# USBHUB.net
KiCad netlist of a schematic drawn in Altium Designer
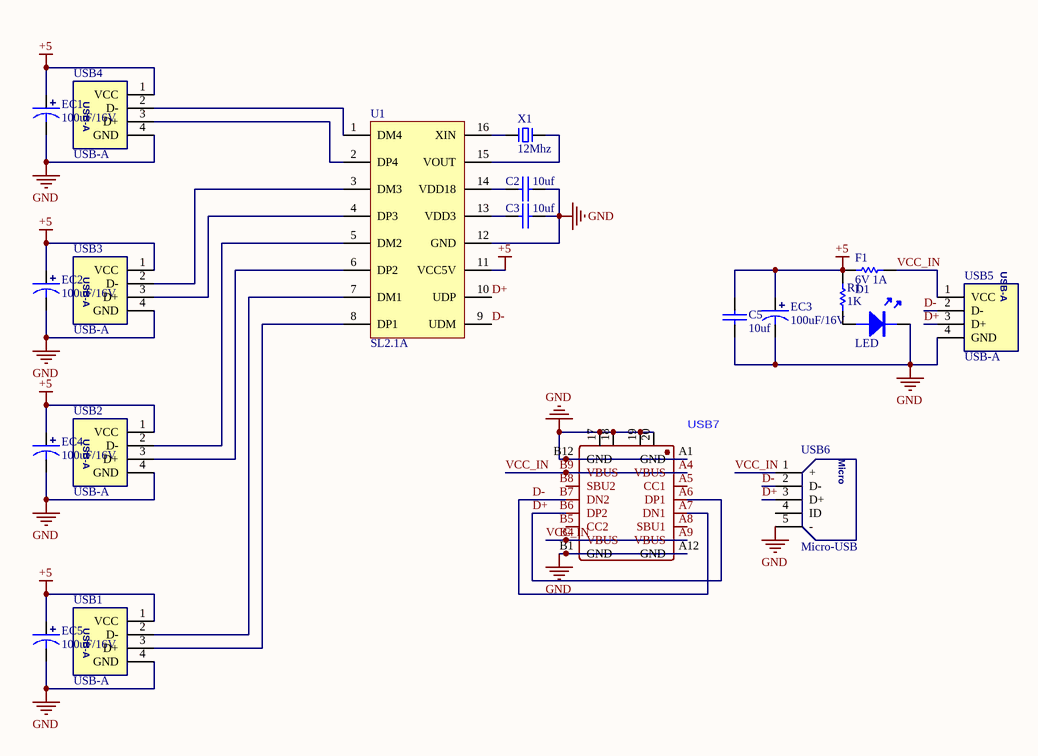
[diagram p0: USBHUB.SchDoc]

(export (version "E")
  (design (tool "Eeschema 10.0.6"))
  (components
    (comp (ref "C2")
      (value "10uf")
      (footprint "0805C")
      (description "无极性电容")
      (libsource (lib "电容") (part "CAP"))
    )
    (comp (ref "C3")
      (value "10uf")
      (footprint "0805C")
      (description "无极性电容")
      (libsource (lib "电容") (part "CAP"))
    )
    (comp (ref "C5")
      (value "10uf")
      (footprint "0805C")
      (description "无极性电容")
      (libsource (lib "电容") (part "CAP"))
    )
    (comp (ref "D1") (value "LED") (footprint "LED-0805R") (libsource (lib "LED") (part "LED")))
    (comp (ref "EC1")
      (value "100uF/16V")
      (footprint "SMD-EC6.3X6.3X10")
      (description "贴片电解电容")
      (libsource (lib "电容") (part "SMD_ECAP"))
    )
    (comp (ref "EC2")
      (value "100uF/16V")
      (footprint "SMD-EC6.3X6.3X10")
      (description "贴片电解电容")
      (libsource (lib "电容") (part "SMD_ECAP"))
    )
    (comp (ref "EC3")
      (value "100uF/16V")
      (footprint "SMD-EC6.3X6.3X10")
      (description "贴片电解电容")
      (libsource (lib "电容") (part "SMD_ECAP"))
    )
    (comp (ref "EC4")
      (value "100uF/16V")
      (footprint "SMD-EC6.3X6.3X10")
      (description "贴片电解电容")
      (libsource (lib "电容") (part "SMD_ECAP"))
    )
    (comp (ref "EC5")
      (value "100uF/16V")
      (footprint "SMD-EC6.3X6.3X10")
      (description "贴片电解电容")
      (libsource (lib "电容") (part "SMD_ECAP"))
    )
    (comp (ref "F1") (value "6V 1A") (footprint "0805R") (libsource (lib "电阻") (part "RES")))
    (comp (ref "R1") (value "1K") (footprint "0805R") (libsource (lib "电阻") (part "RES")))
    (comp (ref "U1") (value "SL2.1A") (footprint "SOP16") (libsource (lib "USBHUB") (part "SL2.1A")))
    (comp (ref "USB1") (value "USB-A") (footprint "USB-A/S_A") (libsource (lib "USB") (part "USB-A")))
    (comp (ref "USB2") (value "USB-A") (footprint "USB-A/S_A") (libsource (lib "USB") (part "USB-A")))
    (comp (ref "USB3") (value "USB-A") (footprint "USB-A/S_A") (libsource (lib "USB") (part "USB-A")))
    (comp (ref "USB4") (value "USB-A") (footprint "USB-A/S_A") (libsource (lib "USB") (part "USB-A")))
    (comp (ref "USB5") (value "USB-A") (footprint "USB-A/S_A") (libsource (lib "") (part "USB-A_1")))
    (comp (ref "USB6")
      (value "Micro-USB")
      (footprint "USB-MICRO_A")
      (libsource (lib "USB") (part "Micro-USB"))
    )
    (comp (ref "USB7")
      (value "~")
      (footprint "TYPE-C")
      (libsource (lib "altium-import") (part "root_0_TYPE-C-16M-0243MD_"))
    )
    (comp (ref "X1")
      (value "12Mhz")
      (footprint "OSC HC-49S")
      (description "2脚无源脚晶振")
      (libsource (lib "晶振") (part "XTAL-2P"))
    )
  )
  (nets
    (net (code "1") (name "+5") (class "Default")
      (node (ref "C5") (pin "2") (pinfunction "2_2") (pintype "passive"))
      (node (ref "EC1") (pin "1") (pinfunction "1_1") (pintype "passive"))
      (node (ref "EC2") (pin "1") (pinfunction "1_1") (pintype "passive"))
      (node (ref "EC3") (pin "1") (pinfunction "1_1") (pintype "passive"))
      (node (ref "EC4") (pin "1") (pinfunction "1_1") (pintype "passive"))
      (node (ref "EC5") (pin "1") (pinfunction "1_1") (pintype "passive"))
      (node (ref "F1") (pin "2") (pinfunction "2_2") (pintype "passive"))
      (node (ref "R1") (pin "2") (pinfunction "2_2") (pintype "passive"))
      (node (ref "U1") (pin "11") (pinfunction "VCC5V_11") (pintype "passive"))
      (node (ref "USB1") (pin "1") (pinfunction "VCC_1") (pintype "passive"))
      (node (ref "USB2") (pin "1") (pinfunction "VCC_1") (pintype "passive"))
      (node (ref "USB3") (pin "1") (pinfunction "VCC_1") (pintype "passive"))
      (node (ref "USB4") (pin "1") (pinfunction "VCC_1") (pintype "passive"))
    )
    (net (code "2") (name "/D+") (class "Default")
      (node (ref "U1") (pin "10") (pinfunction "UDP_10") (pintype "passive"))
      (node (ref "USB5") (pin "3") (pinfunction "D+_3") (pintype "passive"))
      (node (ref "USB6") (pin "3") (pinfunction "D+_3") (pintype "passive"))
      (node (ref "USB7") (pin "A6") (pinfunction "DP1_A6") (pintype "passive"))
      (node (ref "USB7") (pin "B6") (pinfunction "DP2_B6") (pintype "passive"))
    )
    (net (code "3") (name "/D-") (class "Default")
      (node (ref "U1") (pin "9") (pinfunction "UDM_9") (pintype "passive"))
      (node (ref "USB5") (pin "2") (pinfunction "D-_2") (pintype "passive"))
      (node (ref "USB6") (pin "2") (pinfunction "D-_2") (pintype "passive"))
      (node (ref "USB7") (pin "A7") (pinfunction "DN1_A7") (pintype "passive"))
      (node (ref "USB7") (pin "B7") (pinfunction "DN2_B7") (pintype "passive"))
    )
    (net (code "4") (name "/VCC_IN") (class "Default")
      (node (ref "F1") (pin "1") (pinfunction "1_1") (pintype "passive"))
      (node (ref "USB5") (pin "1") (pinfunction "VCC_1") (pintype "passive"))
      (node (ref "USB6") (pin "1") (pinfunction "+_1") (pintype "passive"))
      (node (ref "USB7") (pin "A4") (pinfunction "VBUS_A4") (pintype "passive"))
      (node (ref "USB7") (pin "A9") (pinfunction "VBUS_A9") (pintype "passive"))
      (node (ref "USB7") (pin "B4") (pinfunction "VBUS_B4") (pintype "passive"))
      (node (ref "USB7") (pin "B9") (pinfunction "VBUS_B9") (pintype "passive"))
    )
    (net (code "5") (name "GND") (class "Default")
      (node (ref "C2") (pin "1") (pinfunction "1_1") (pintype "passive"))
      (node (ref "C3") (pin "1") (pinfunction "1_1") (pintype "passive"))
      (node (ref "C5") (pin "1") (pinfunction "1_1") (pintype "passive"))
      (node (ref "D1") (pin "K") (pinfunction "K_K") (pintype "passive"))
      (node (ref "EC1") (pin "2") (pinfunction "2_2") (pintype "passive"))
      (node (ref "EC2") (pin "2") (pinfunction "2_2") (pintype "passive"))
      (node (ref "EC3") (pin "2") (pinfunction "2_2") (pintype "passive"))
      (node (ref "EC4") (pin "2") (pinfunction "2_2") (pintype "passive"))
      (node (ref "EC5") (pin "2") (pinfunction "2_2") (pintype "passive"))
      (node (ref "U1") (pin "12") (pinfunction "GND_12") (pintype "passive"))
      (node (ref "USB1") (pin "4") (pinfunction "GND_4") (pintype "passive"))
      (node (ref "USB2") (pin "4") (pinfunction "GND_4") (pintype "passive"))
      (node (ref "USB3") (pin "4") (pinfunction "GND_4") (pintype "passive"))
      (node (ref "USB4") (pin "4") (pinfunction "GND_4") (pintype "passive"))
      (node (ref "USB5") (pin "4") (pinfunction "GND_4") (pintype "passive"))
      (node (ref "USB6") (pin "5") (pinfunction "-_5") (pintype "passive"))
      (node (ref "USB7") (pin "17") (pinfunction "17_17") (pintype "passive"))
      (node (ref "USB7") (pin "18") (pinfunction "18_18") (pintype "passive"))
      (node (ref "USB7") (pin "19") (pinfunction "19_19") (pintype "passive"))
      (node (ref "USB7") (pin "20") (pinfunction "20_20") (pintype "passive"))
      (node (ref "USB7") (pin "A1") (pinfunction "GND_A1") (pintype "passive"))
      (node (ref "USB7") (pin "A12") (pinfunction "GND_A12") (pintype "passive"))
      (node (ref "USB7") (pin "B1") (pinfunction "GND_B1") (pintype "passive"))
      (node (ref "USB7") (pin "B12") (pinfunction "GND_B12") (pintype "passive"))
    )
    (net (code "6") (name "Net-(D1-PadA)") (class "Default")
      (node (ref "D1") (pin "A") (pinfunction "A_A") (pintype "passive"))
      (node (ref "R1") (pin "1") (pinfunction "1_1") (pintype "passive"))
    )
    (net (code "7") (name "Net-(U1-DM1)") (class "Default")
      (node (ref "U1") (pin "7") (pinfunction "DM1_7") (pintype "passive"))
      (node (ref "USB1") (pin "2") (pinfunction "D-_2") (pintype "passive"))
    )
    (net (code "8") (name "Net-(U1-DM2)") (class "Default")
      (node (ref "U1") (pin "5") (pinfunction "DM2_5") (pintype "passive"))
      (node (ref "USB2") (pin "2") (pinfunction "D-_2") (pintype "passive"))
    )
    (net (code "9") (name "Net-(U1-DM3)") (class "Default")
      (node (ref "U1") (pin "3") (pinfunction "DM3_3") (pintype "passive"))
      (node (ref "USB3") (pin "2") (pinfunction "D-_2") (pintype "passive"))
    )
    (net (code "10") (name "Net-(U1-DM4)") (class "Default")
      (node (ref "U1") (pin "1") (pinfunction "DM4_1") (pintype "passive"))
      (node (ref "USB4") (pin "2") (pinfunction "D-_2") (pintype "passive"))
    )
    (net (code "11") (name "Net-(U1-DP1)") (class "Default")
      (node (ref "U1") (pin "8") (pinfunction "DP1_8") (pintype "passive"))
      (node (ref "USB1") (pin "3") (pinfunction "D+_3") (pintype "passive"))
    )
    (net (code "12") (name "Net-(U1-DP2)") (class "Default")
      (node (ref "U1") (pin "6") (pinfunction "DP2_6") (pintype "passive"))
      (node (ref "USB2") (pin "3") (pinfunction "D+_3") (pintype "passive"))
    )
    (net (code "13") (name "Net-(U1-DP3)") (class "Default")
      (node (ref "U1") (pin "4") (pinfunction "DP3_4") (pintype "passive"))
      (node (ref "USB3") (pin "3") (pinfunction "D+_3") (pintype "passive"))
    )
    (net (code "14") (name "Net-(U1-DP4)") (class "Default")
      (node (ref "U1") (pin "2") (pinfunction "DP4_2") (pintype "passive"))
      (node (ref "USB4") (pin "3") (pinfunction "D+_3") (pintype "passive"))
    )
    (net (code "15") (name "Net-(U1-VDD3)") (class "Default")
      (node (ref "C3") (pin "2") (pinfunction "2_2") (pintype "passive"))
      (node (ref "U1") (pin "13") (pinfunction "VDD3_13") (pintype "passive"))
    )
    (net (code "16") (name "Net-(U1-VDD18)") (class "Default")
      (node (ref "C2") (pin "2") (pinfunction "2_2") (pintype "passive"))
      (node (ref "U1") (pin "14") (pinfunction "VDD18_14") (pintype "passive"))
    )
    (net (code "17") (name "Net-(U1-VOUT)") (class "Default")
      (node (ref "U1") (pin "15") (pinfunction "VOUT_15") (pintype "passive"))
      (node (ref "X1") (pin "2") (pinfunction "2_2") (pintype "passive"))
    )
    (net (code "18") (name "Net-(U1-XIN)") (class "Default")
      (node (ref "U1") (pin "16") (pinfunction "XIN_16") (pintype "passive"))
      (node (ref "X1") (pin "1") (pinfunction "1_1") (pintype "passive"))
    )
    (net (code "19") (name "unconnected-(USB6-ID-Pad4)") (class "Default")
      (node (ref "USB6") (pin "4") (pinfunction "ID_4") (pintype "passive"))
    )
    (net (code "20") (name "unconnected-(USB7-CC1-PadA5)") (class "Default")
      (node (ref "USB7") (pin "A5") (pinfunction "CC1_A5") (pintype "passive"))
    )
    (net (code "21") (name "unconnected-(USB7-CC2-PadB5)") (class "Default")
      (node (ref "USB7") (pin "B5") (pinfunction "CC2_B5") (pintype "passive"))
    )
    (net (code "22") (name "unconnected-(USB7-SBU1-PadA8)") (class "Default")
      (node (ref "USB7") (pin "A8") (pinfunction "SBU1_A8") (pintype "passive"))
    )
    (net (code "23") (name "unconnected-(USB7-SBU2-PadB8)") (class "Default")
      (node (ref "USB7") (pin "B8") (pinfunction "SBU2_B8") (pintype "passive"))
    )
  )
)
